# PSU.net
KiCad netlist of a schematic drawn in EasyEDA
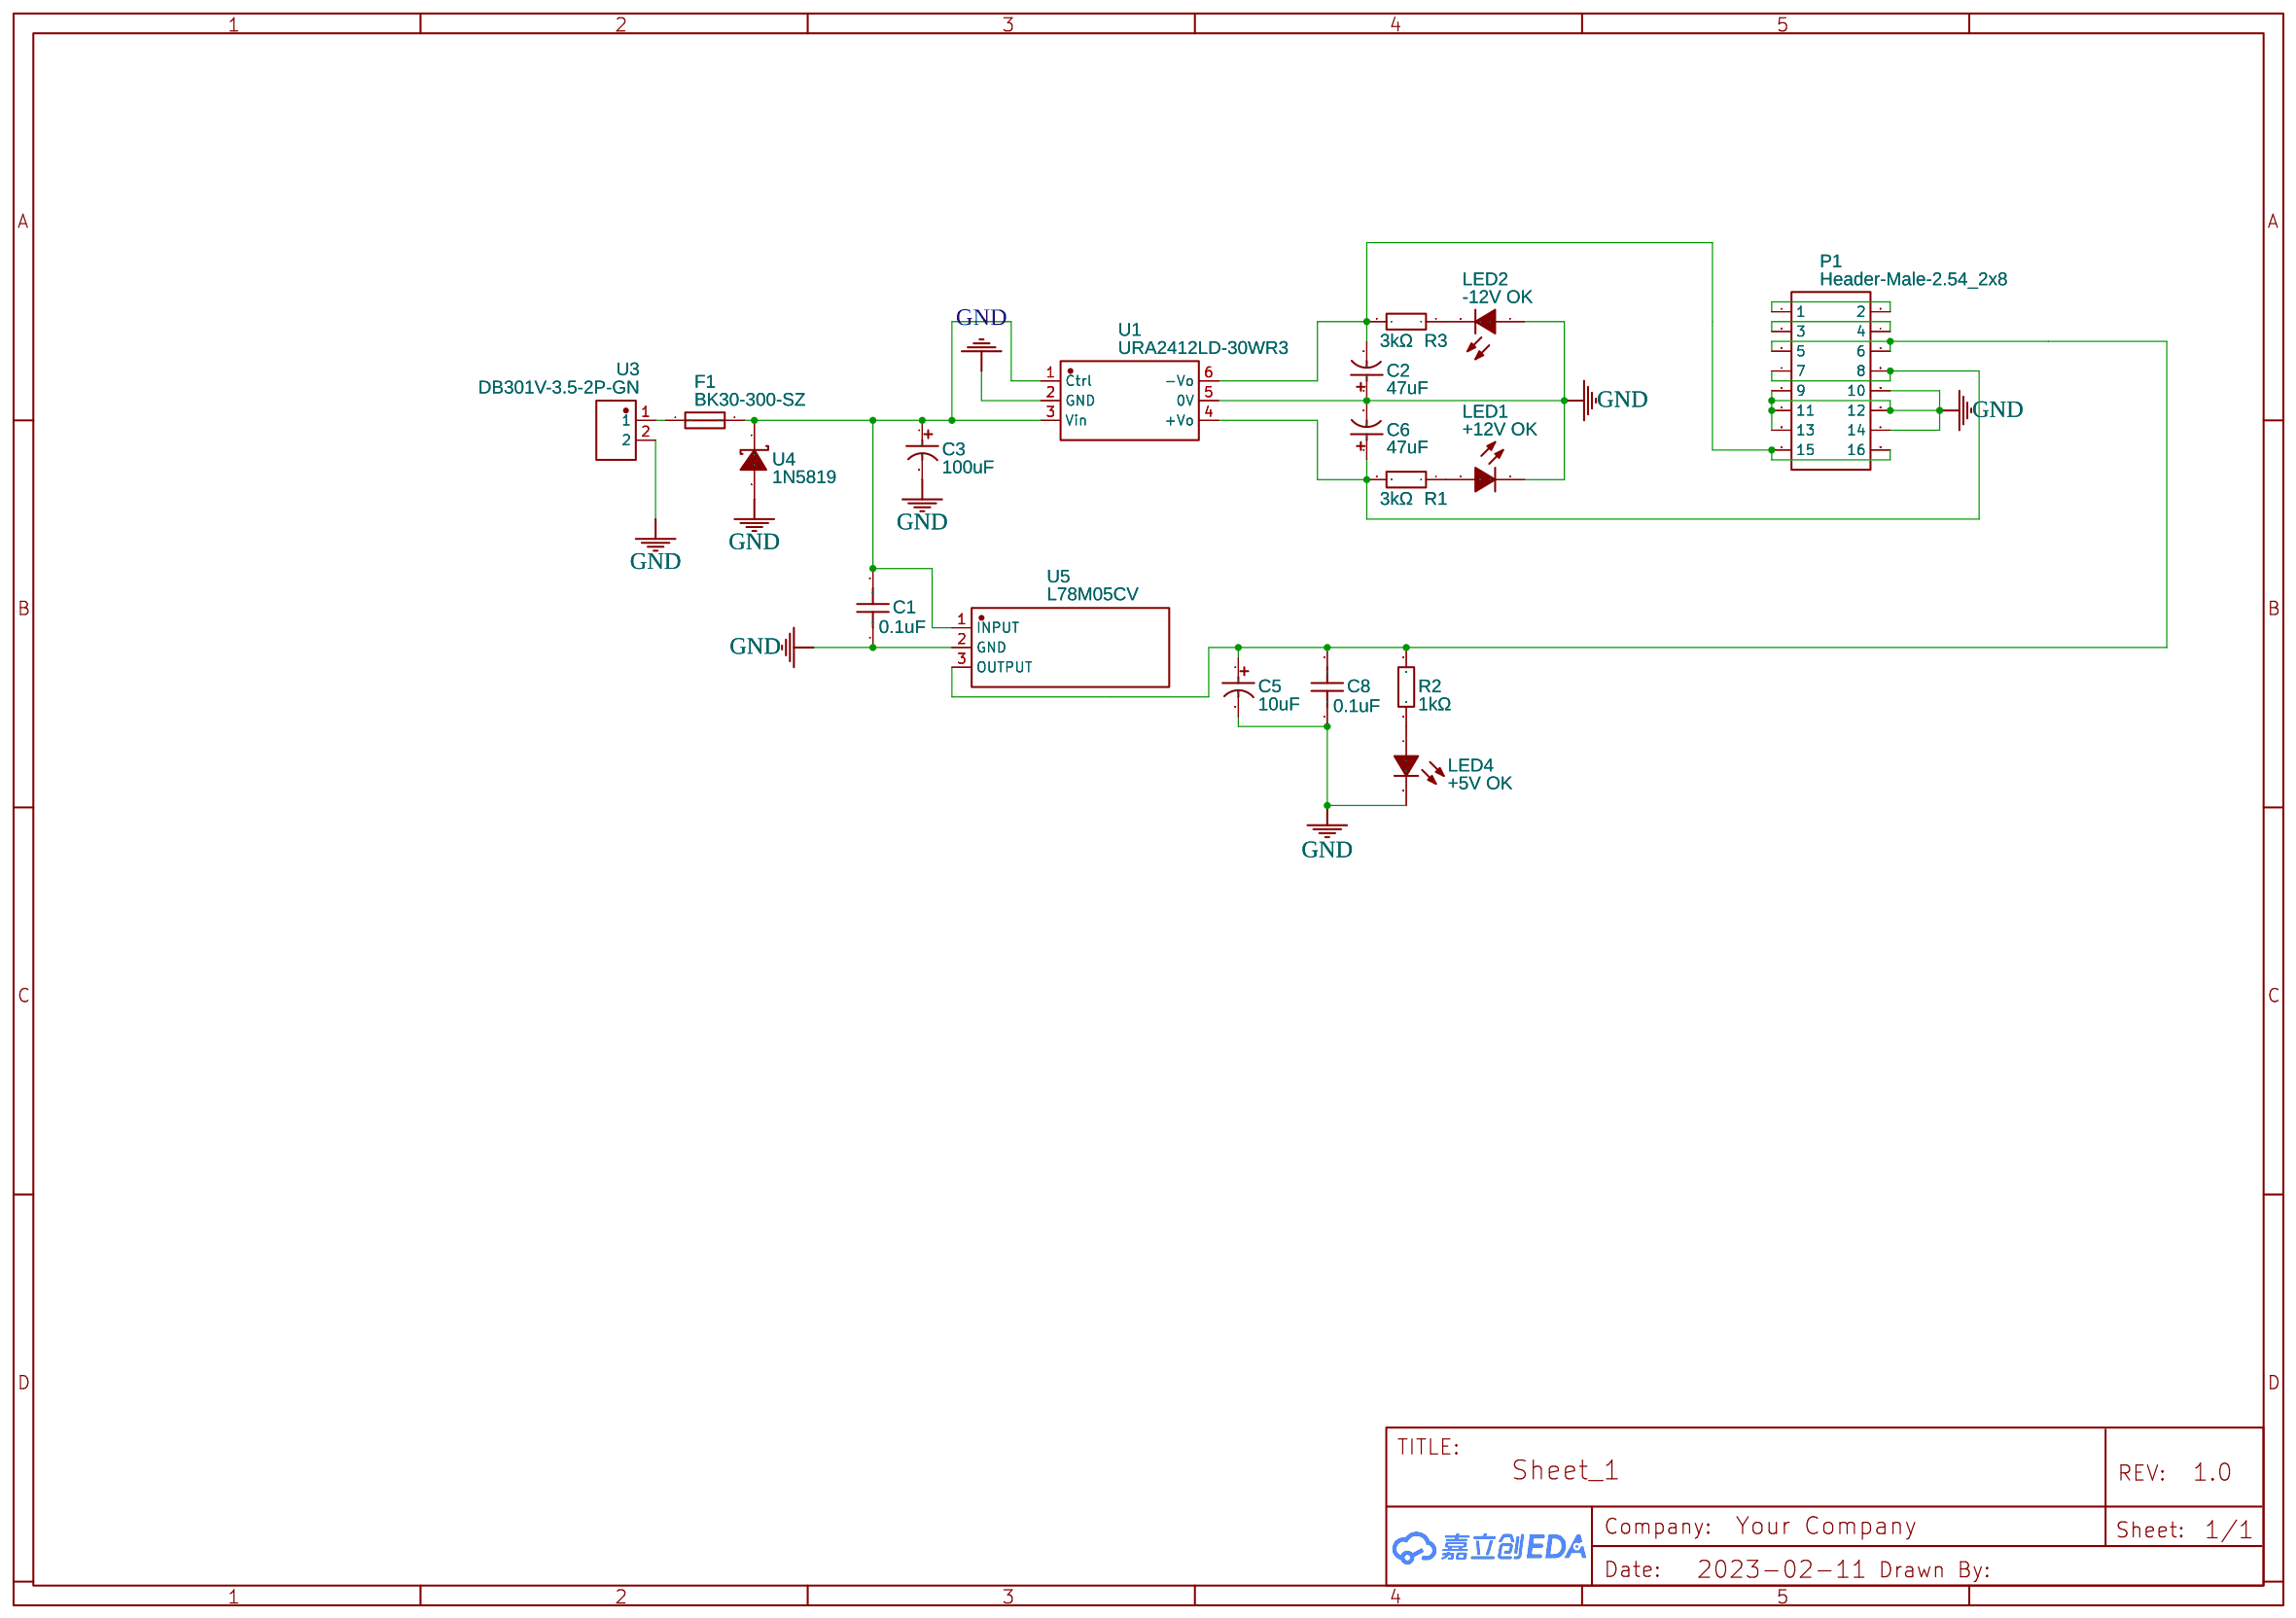
[diagram p0: schematic sheet]

(export (version "E")
  (design (tool "Eeschema 10.0.6"))
  (components
    (comp (ref "C1")
      (value "0.1uF")
      (fields
        (field (name "BOM_Manufacturer Part") "MPE103J100V82CL0048")
        (field (name "BOM_Supplier Part") "C2803188")
      )
      (libsource (lib "") (part "MPE103J100V82CL0048"))
    )
    (comp (ref "C2")
      (value "47uF")
      (fields
        (field (name "BOM_Manufacturer Part") "25YXF47MEFC5X11")
        (field (name "BOM_Supplier Part") "C88724")
      )
      (libsource (lib "") (part "25YXF47MEFC5X11"))
    )
    (comp (ref "C3")
      (value "100uF")
      (fields
        (field (name "BOM_Manufacturer Part") "50YXJ100M8X11.5")
        (field (name "BOM_Supplier Part") "C88859")
      )
      (libsource (lib "") (part "50YXJ100M8X11.5"))
    )
    (comp (ref "C5")
      (value "10uF")
      (fields
        (field (name "BOM_Manufacturer Part") "25MS710MEFC4X7")
        (field (name "BOM_Supplier Part") "C88739")
      )
      (libsource (lib "") (part "25MS710MEFC4X7"))
    )
    (comp (ref "C6")
      (value "47uF")
      (fields
        (field (name "BOM_Manufacturer Part") "25YXF47MEFC5X11")
        (field (name "BOM_Supplier Part") "C88724")
      )
      (libsource (lib "") (part "25YXF47MEFC5X11"))
    )
    (comp (ref "C8")
      (value "0.1uF")
      (fields
        (field (name "BOM_Manufacturer Part") "MPE103J100V82CL0048")
        (field (name "BOM_Supplier Part") "C2803188")
      )
      (libsource (lib "") (part "MPE103J100V82CL0048"))
    )
    (comp (ref "F1")
      (value "BK30-300-SZ")
      (fields (field (name "BOM_Supplier Part") "C194051"))
      (libsource (lib "") (part "BK30-300-SZ"))
    )
    (comp (ref "LED1")
      (value "+12V OK")
      (fields
        (field (name "BOM_Manufacturer Part") "204-10SURD/S530-A3-L")
        (field (name "BOM_Supplier Part") "C99771")
      )
      (libsource (lib "") (part "204-10SURD/S530-A3-L_1"))
    )
    (comp (ref "LED2")
      (value "-12V OK")
      (fields
        (field (name "BOM_Manufacturer Part") "204-10SURD/S530-A3-L")
        (field (name "BOM_Supplier Part") "C99771")
      )
      (libsource (lib "") (part "204-10SURD/S530-A3-L"))
    )
    (comp (ref "LED4")
      (value "+5V OK")
      (fields
        (field (name "BOM_Manufacturer Part") "204-10SURD/S530-A3-L")
        (field (name "BOM_Supplier Part") "C99771")
      )
      (libsource (lib "") (part "204-10SURD/S530-A3-L_2"))
    )
    (comp (ref "P1")
      (value "Header-Male-2.54_2x8")
      (fields (field (name "BOM_Manufacturer Part") "2.54-2*8P针") (field (name "BOM_Supplier Part") "C68234"))
      (libsource (lib "") (part "Header-Male-2.54_2x8"))
    )
    (comp (ref "R1")
      (value "3kΩ")
      (fields
        (field (name "BOM_Manufacturer Part") "MFR0W8F1001A50")
        (field (name "BOM_Supplier Part") "C58674")
      )
      (libsource (lib "") (part "MFR0W8F1001A50"))
    )
    (comp (ref "R2")
      (value "1kΩ")
      (fields
        (field (name "BOM_Manufacturer Part") "MFR0W8F1001A50")
        (field (name "BOM_Supplier Part") "C58674")
      )
      (libsource (lib "") (part "MFR0W8F1001A50_1"))
    )
    (comp (ref "R3")
      (value "3kΩ")
      (fields
        (field (name "BOM_Manufacturer Part") "MFR0W8F1001A50")
        (field (name "BOM_Supplier Part") "C58674")
      )
      (libsource (lib "") (part "MFR0W8F1001A50"))
    )
    (comp (ref "U1")
      (value "URA2412LD-30WR3")
      (fields (field (name "BOM_Supplier Part") "C2757488"))
      (libsource (lib "") (part "URA2412LD-30WR3"))
    )
    (comp (ref "U3")
      (value "DB301V-3.5-2P-GN")
      (fields (field (name "BOM_Supplier Part") "C695629"))
      (libsource (lib "") (part "DB301V-3.5-2P-GN"))
    )
    (comp (ref "U4")
      (value "1N5819")
      (fields (field (name "BOM_Supplier Part") "C3039965"))
      (libsource (lib "") (part "1N5819_C3039965"))
    )
    (comp (ref "U5")
      (value "L78M05CV")
      (fields (field (name "BOM_Supplier Part") "C283462"))
      (libsource (lib "") (part "L78M05CV"))
    )
  )
  (nets
    (net (code "1") (name "GND") (class "Default")
      (node (ref "C1") (pin "1") (pinfunction "1_1") (pintype "unspecified"))
      (node (ref "C2") (pin "1") (pinfunction "1_1") (pintype "input"))
      (node (ref "C3") (pin "2") (pinfunction "2_2") (pintype "input"))
      (node (ref "C5") (pin "2") (pinfunction "2_2") (pintype "input"))
      (node (ref "C6") (pin "2") (pinfunction "2_2") (pintype "input"))
      (node (ref "C8") (pin "1") (pinfunction "1_1") (pintype "unspecified"))
      (node (ref "LED1") (pin "2") (pinfunction "K_2") (pintype "input"))
      (node (ref "LED2") (pin "1") (pinfunction "A_1") (pintype "input"))
      (node (ref "LED4") (pin "2") (pinfunction "K_2") (pintype "input"))
      (node (ref "P1") (pin "10") (pinfunction "10_10") (pintype "input"))
      (node (ref "P1") (pin "11") (pinfunction "11_11") (pintype "input"))
      (node (ref "P1") (pin "12") (pinfunction "12_12") (pintype "input"))
      (node (ref "P1") (pin "13") (pinfunction "13_13") (pintype "input"))
      (node (ref "P1") (pin "14") (pinfunction "14_14") (pintype "input"))
      (node (ref "P1") (pin "9") (pinfunction "9_9") (pintype "input"))
      (node (ref "U1") (pin "2") (pinfunction "GND_2") (pintype "unspecified"))
      (node (ref "U1") (pin "5") (pinfunction "0V_5") (pintype "unspecified"))
      (node (ref "U3") (pin "2") (pinfunction "2_2") (pintype "unspecified"))
      (node (ref "U4") (pin "2") (pinfunction "A_2") (pintype "unspecified"))
      (node (ref "U5") (pin "2") (pinfunction "GND_2") (pintype "unspecified"))
    )
    (net (code "2") (name "Net-(F1-Pad1)") (class "Default")
      (node (ref "F1") (pin "1") (pinfunction "1_1") (pintype "unspecified"))
      (node (ref "U3") (pin "1") (pinfunction "1_1") (pintype "unspecified"))
    )
    (net (code "3") (name "Net-(LED1-A)") (class "Default")
      (node (ref "LED1") (pin "1") (pinfunction "A_1") (pintype "input"))
      (node (ref "R1") (pin "1") (pinfunction "1_1") (pintype "input"))
    )
    (net (code "4") (name "Net-(LED2-K)") (class "Default")
      (node (ref "LED2") (pin "2") (pinfunction "K_2") (pintype "input"))
      (node (ref "R3") (pin "1") (pinfunction "1_1") (pintype "input"))
    )
    (net (code "5") (name "Net-(LED4-A)") (class "Default")
      (node (ref "LED4") (pin "1") (pinfunction "A_1") (pintype "input"))
      (node (ref "R2") (pin "1") (pinfunction "1_1") (pintype "input"))
    )
    (net (code "6") (name "Net-(P1-Pad1)") (class "Default")
      (node (ref "P1") (pin "1") (pinfunction "1_1") (pintype "input"))
      (node (ref "P1") (pin "2") (pinfunction "2_2") (pintype "input"))
    )
    (net (code "7") (name "Net-(P1-Pad3)") (class "Default")
      (node (ref "P1") (pin "3") (pinfunction "3_3") (pintype "input"))
      (node (ref "P1") (pin "4") (pinfunction "4_4") (pintype "input"))
    )
    (net (code "8") (name "Net-(U1-+Vo)") (class "Default")
      (node (ref "C6") (pin "1") (pinfunction "1_1") (pintype "input"))
      (node (ref "P1") (pin "7") (pinfunction "7_7") (pintype "input"))
      (node (ref "P1") (pin "8") (pinfunction "8_8") (pintype "input"))
      (node (ref "R1") (pin "2") (pinfunction "2_2") (pintype "input"))
      (node (ref "U1") (pin "4") (pinfunction "+Vo_4") (pintype "unspecified"))
    )
    (net (code "9") (name "Net-(U1--Vo)") (class "Default")
      (node (ref "C2") (pin "2") (pinfunction "2_2") (pintype "input"))
      (node (ref "P1") (pin "15") (pinfunction "15_15") (pintype "input"))
      (node (ref "P1") (pin "16") (pinfunction "16_16") (pintype "input"))
      (node (ref "R3") (pin "2") (pinfunction "2_2") (pintype "input"))
      (node (ref "U1") (pin "6") (pinfunction "-Vo_6") (pintype "unspecified"))
    )
    (net (code "10") (name "Net-(U1-Ctrl)") (class "Default")
      (node (ref "C1") (pin "2") (pinfunction "2_2") (pintype "unspecified"))
      (node (ref "C3") (pin "1") (pinfunction "1_1") (pintype "input"))
      (node (ref "F1") (pin "2") (pinfunction "2_2") (pintype "unspecified"))
      (node (ref "U1") (pin "1") (pinfunction "Ctrl_1") (pintype "unspecified"))
      (node (ref "U1") (pin "3") (pinfunction "Vin_3") (pintype "unspecified"))
      (node (ref "U4") (pin "1") (pinfunction "K_1") (pintype "unspecified"))
      (node (ref "U5") (pin "1") (pinfunction "INPUT_1") (pintype "unspecified"))
    )
    (net (code "11") (name "Net-(U5-OUTPUT)") (class "Default")
      (node (ref "C5") (pin "1") (pinfunction "1_1") (pintype "input"))
      (node (ref "C8") (pin "2") (pinfunction "2_2") (pintype "unspecified"))
      (node (ref "P1") (pin "5") (pinfunction "5_5") (pintype "input"))
      (node (ref "P1") (pin "6") (pinfunction "6_6") (pintype "input"))
      (node (ref "R2") (pin "2") (pinfunction "2_2") (pintype "input"))
      (node (ref "U5") (pin "3") (pinfunction "OUTPUT_3") (pintype "unspecified"))
    )
  )
)
